# hvreg.net
KiCad netlist of a schematic drawn in EAGLE
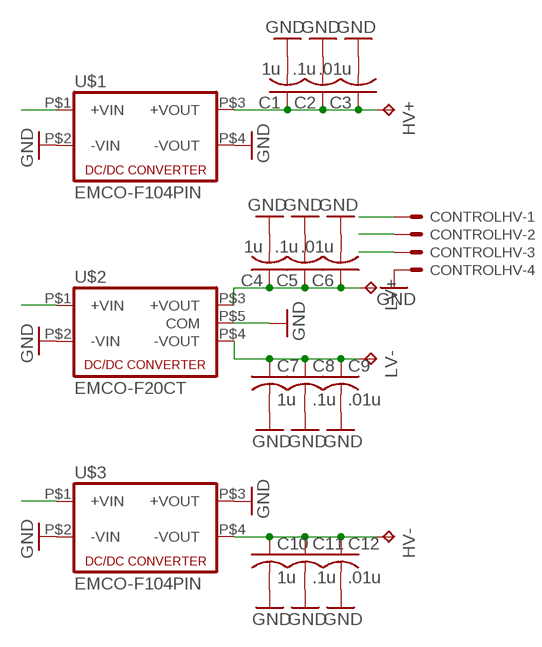
[diagram p0: schematic, sheet 1]

(export (version "E")
  (design (tool "Eeschema 10.0.6"))
  (components
    (comp (ref "C1")
      (value "1u")
      (footprint "eagle-import:C275-113X316")
      (libsource (lib "eagle-import") (part "C-US275-113X316"))
    )
    (comp (ref "C2")
      (value ".1u")
      (footprint "eagle-import:C102-043X133")
      (libsource (lib "eagle-import") (part "C-US102-043X133"))
    )
    (comp (ref "C3")
      (value ".01u")
      (footprint "eagle-import:C075-042X103")
      (libsource (lib "eagle-import") (part "C-US075-042X103"))
    )
    (comp (ref "C4")
      (value "1u")
      (footprint "eagle-import:C275-113X316")
      (libsource (lib "eagle-import") (part "C-US275-113X316"))
    )
    (comp (ref "C5")
      (value ".1u")
      (footprint "eagle-import:C102-043X133")
      (libsource (lib "eagle-import") (part "C-US102-043X133"))
    )
    (comp (ref "C6")
      (value ".01u")
      (footprint "eagle-import:C075-042X103")
      (libsource (lib "eagle-import") (part "C-US075-042X103"))
    )
    (comp (ref "C7")
      (value "1u")
      (footprint "eagle-import:C275-113X316")
      (libsource (lib "eagle-import") (part "C-US275-113X316"))
    )
    (comp (ref "C8")
      (value ".1u")
      (footprint "eagle-import:C102-043X133")
      (libsource (lib "eagle-import") (part "C-US102-043X133"))
    )
    (comp (ref "C9")
      (value ".01u")
      (footprint "eagle-import:C075-042X103")
      (libsource (lib "eagle-import") (part "C-US075-042X103"))
    )
    (comp (ref "C10")
      (value "1u")
      (footprint "eagle-import:C275-113X316")
      (libsource (lib "eagle-import") (part "C-US275-113X316"))
    )
    (comp (ref "C11")
      (value ".1u")
      (footprint "eagle-import:C102-043X133")
      (libsource (lib "eagle-import") (part "C-US102-043X133"))
    )
    (comp (ref "C12")
      (value ".01u")
      (footprint "eagle-import:C075-042X103")
      (libsource (lib "eagle-import") (part "C-US075-042X103"))
    )
    (comp (ref "CONTROLHV")
      (value "KK-156-4")
      (footprint "eagle-import:KK-156-4")
      (libsource (lib "eagle-import") (part "KK-156-4"))
    )
    (comp (ref "HV+")
      (value "TPPAD1-20Y")
      (footprint "eagle-import:P1-20Y")
      (libsource (lib "eagle-import") (part "TPPAD1-20Y"))
    )
    (comp (ref "HV-")
      (value "TPPAD1-20Y")
      (footprint "eagle-import:P1-20Y")
      (libsource (lib "eagle-import") (part "TPPAD1-20Y"))
    )
    (comp (ref "LV+")
      (value "TPPAD1-20Y")
      (footprint "eagle-import:P1-20Y")
      (libsource (lib "eagle-import") (part "TPPAD1-20Y"))
    )
    (comp (ref "LV-")
      (value "TPPAD1-20Y")
      (footprint "eagle-import:P1-20Y")
      (libsource (lib "eagle-import") (part "TPPAD1-20Y"))
    )
    (comp (ref "U$1")
      (value "EMCO-F104PIN")
      (footprint "eagle-import:EMCO-F")
      (libsource (lib "eagle-import") (part "EMCO-F104PIN"))
    )
    (comp (ref "U$2")
      (value "EMCO-F20CT")
      (footprint "eagle-import:EMCO-F_CT")
      (libsource (lib "eagle-import") (part "EMCO-F20CT"))
    )
    (comp (ref "U$3")
      (value "EMCO-F104PIN")
      (footprint "eagle-import:EMCO-F")
      (libsource (lib "eagle-import") (part "EMCO-F104PIN"))
    )
  )
  (nets
    (net (code "1") (name "/VREG1") (class "Default")
      (node (ref "CONTROLHV") (pin "1") (pinfunction "S_1") (pintype "passive"))
      (node (ref "U$1") (pin "P$1") (pinfunction "+VIN_P$1") (pintype "passive"))
    )
    (net (code "2") (name "/VREG2") (class "Default")
      (node (ref "CONTROLHV") (pin "2") (pinfunction "S_2") (pintype "passive"))
      (node (ref "U$2") (pin "P$1") (pinfunction "+VIN_P$1") (pintype "passive"))
    )
    (net (code "3") (name "/VREG3") (class "Default")
      (node (ref "CONTROLHV") (pin "3") (pinfunction "S_3") (pintype "passive"))
      (node (ref "U$3") (pin "P$1") (pinfunction "+VIN_P$1") (pintype "passive"))
    )
    (net (code "4") (name "GND") (class "Default")
      (node (ref "C1") (pin "2") (pinfunction "2_2") (pintype "passive"))
      (node (ref "C10") (pin "2") (pinfunction "2_2") (pintype "passive"))
      (node (ref "C11") (pin "2") (pinfunction "2_2") (pintype "passive"))
      (node (ref "C12") (pin "2") (pinfunction "2_2") (pintype "passive"))
      (node (ref "C2") (pin "2") (pinfunction "2_2") (pintype "passive"))
      (node (ref "C3") (pin "2") (pinfunction "2_2") (pintype "passive"))
      (node (ref "C4") (pin "2") (pinfunction "2_2") (pintype "passive"))
      (node (ref "C5") (pin "2") (pinfunction "2_2") (pintype "passive"))
      (node (ref "C6") (pin "2") (pinfunction "2_2") (pintype "passive"))
      (node (ref "C7") (pin "2") (pinfunction "2_2") (pintype "passive"))
      (node (ref "C8") (pin "2") (pinfunction "2_2") (pintype "passive"))
      (node (ref "C9") (pin "2") (pinfunction "2_2") (pintype "passive"))
      (node (ref "CONTROLHV") (pin "4") (pinfunction "S_4") (pintype "passive"))
      (node (ref "U$1") (pin "P$2") (pinfunction "-VIN_P$2") (pintype "passive"))
      (node (ref "U$1") (pin "P$4") (pinfunction "-VOUT_P$4") (pintype "passive"))
      (node (ref "U$2") (pin "P$2") (pinfunction "-VIN_P$2") (pintype "passive"))
      (node (ref "U$2") (pin "P$5") (pinfunction "COM_P$5") (pintype "passive"))
      (node (ref "U$3") (pin "P$2") (pinfunction "-VIN_P$2") (pintype "passive"))
      (node (ref "U$3") (pin "P$3") (pinfunction "+VOUT_P$3") (pintype "passive"))
    )
    (net (code "5") (name "Net-(U$1-+VOUT)") (class "Default")
      (node (ref "C1") (pin "1") (pinfunction "1_1") (pintype "passive"))
      (node (ref "C2") (pin "1") (pinfunction "1_1") (pintype "passive"))
      (node (ref "C3") (pin "1") (pinfunction "1_1") (pintype "passive"))
      (node (ref "HV+") (pin "TP") (pinfunction "TP_TP") (pintype "input"))
      (node (ref "U$1") (pin "P$3") (pinfunction "+VOUT_P$3") (pintype "passive"))
    )
    (net (code "6") (name "Net-(U$2-+VOUT)") (class "Default")
      (node (ref "C4") (pin "1") (pinfunction "1_1") (pintype "passive"))
      (node (ref "C5") (pin "1") (pinfunction "1_1") (pintype "passive"))
      (node (ref "C6") (pin "1") (pinfunction "1_1") (pintype "passive"))
      (node (ref "LV+") (pin "TP") (pinfunction "TP_TP") (pintype "input"))
      (node (ref "U$2") (pin "P$3") (pinfunction "+VOUT_P$3") (pintype "passive"))
    )
    (net (code "7") (name "Net-(U$2--VOUT)") (class "Default")
      (node (ref "C7") (pin "1") (pinfunction "1_1") (pintype "passive"))
      (node (ref "C8") (pin "1") (pinfunction "1_1") (pintype "passive"))
      (node (ref "C9") (pin "1") (pinfunction "1_1") (pintype "passive"))
      (node (ref "LV-") (pin "TP") (pinfunction "TP_TP") (pintype "input"))
      (node (ref "U$2") (pin "P$4") (pinfunction "-VOUT_P$4") (pintype "passive"))
    )
    (net (code "8") (name "Net-(U$3--VOUT)") (class "Default")
      (node (ref "C10") (pin "1") (pinfunction "1_1") (pintype "passive"))
      (node (ref "C11") (pin "1") (pinfunction "1_1") (pintype "passive"))
      (node (ref "C12") (pin "1") (pinfunction "1_1") (pintype "passive"))
      (node (ref "HV-") (pin "TP") (pinfunction "TP_TP") (pintype "input"))
      (node (ref "U$3") (pin "P$4") (pinfunction "-VOUT_P$4") (pintype "passive"))
    )
  )
)
